# ICAN-7006-STM.net
KiCad netlist of a schematic drawn in Altium Designer
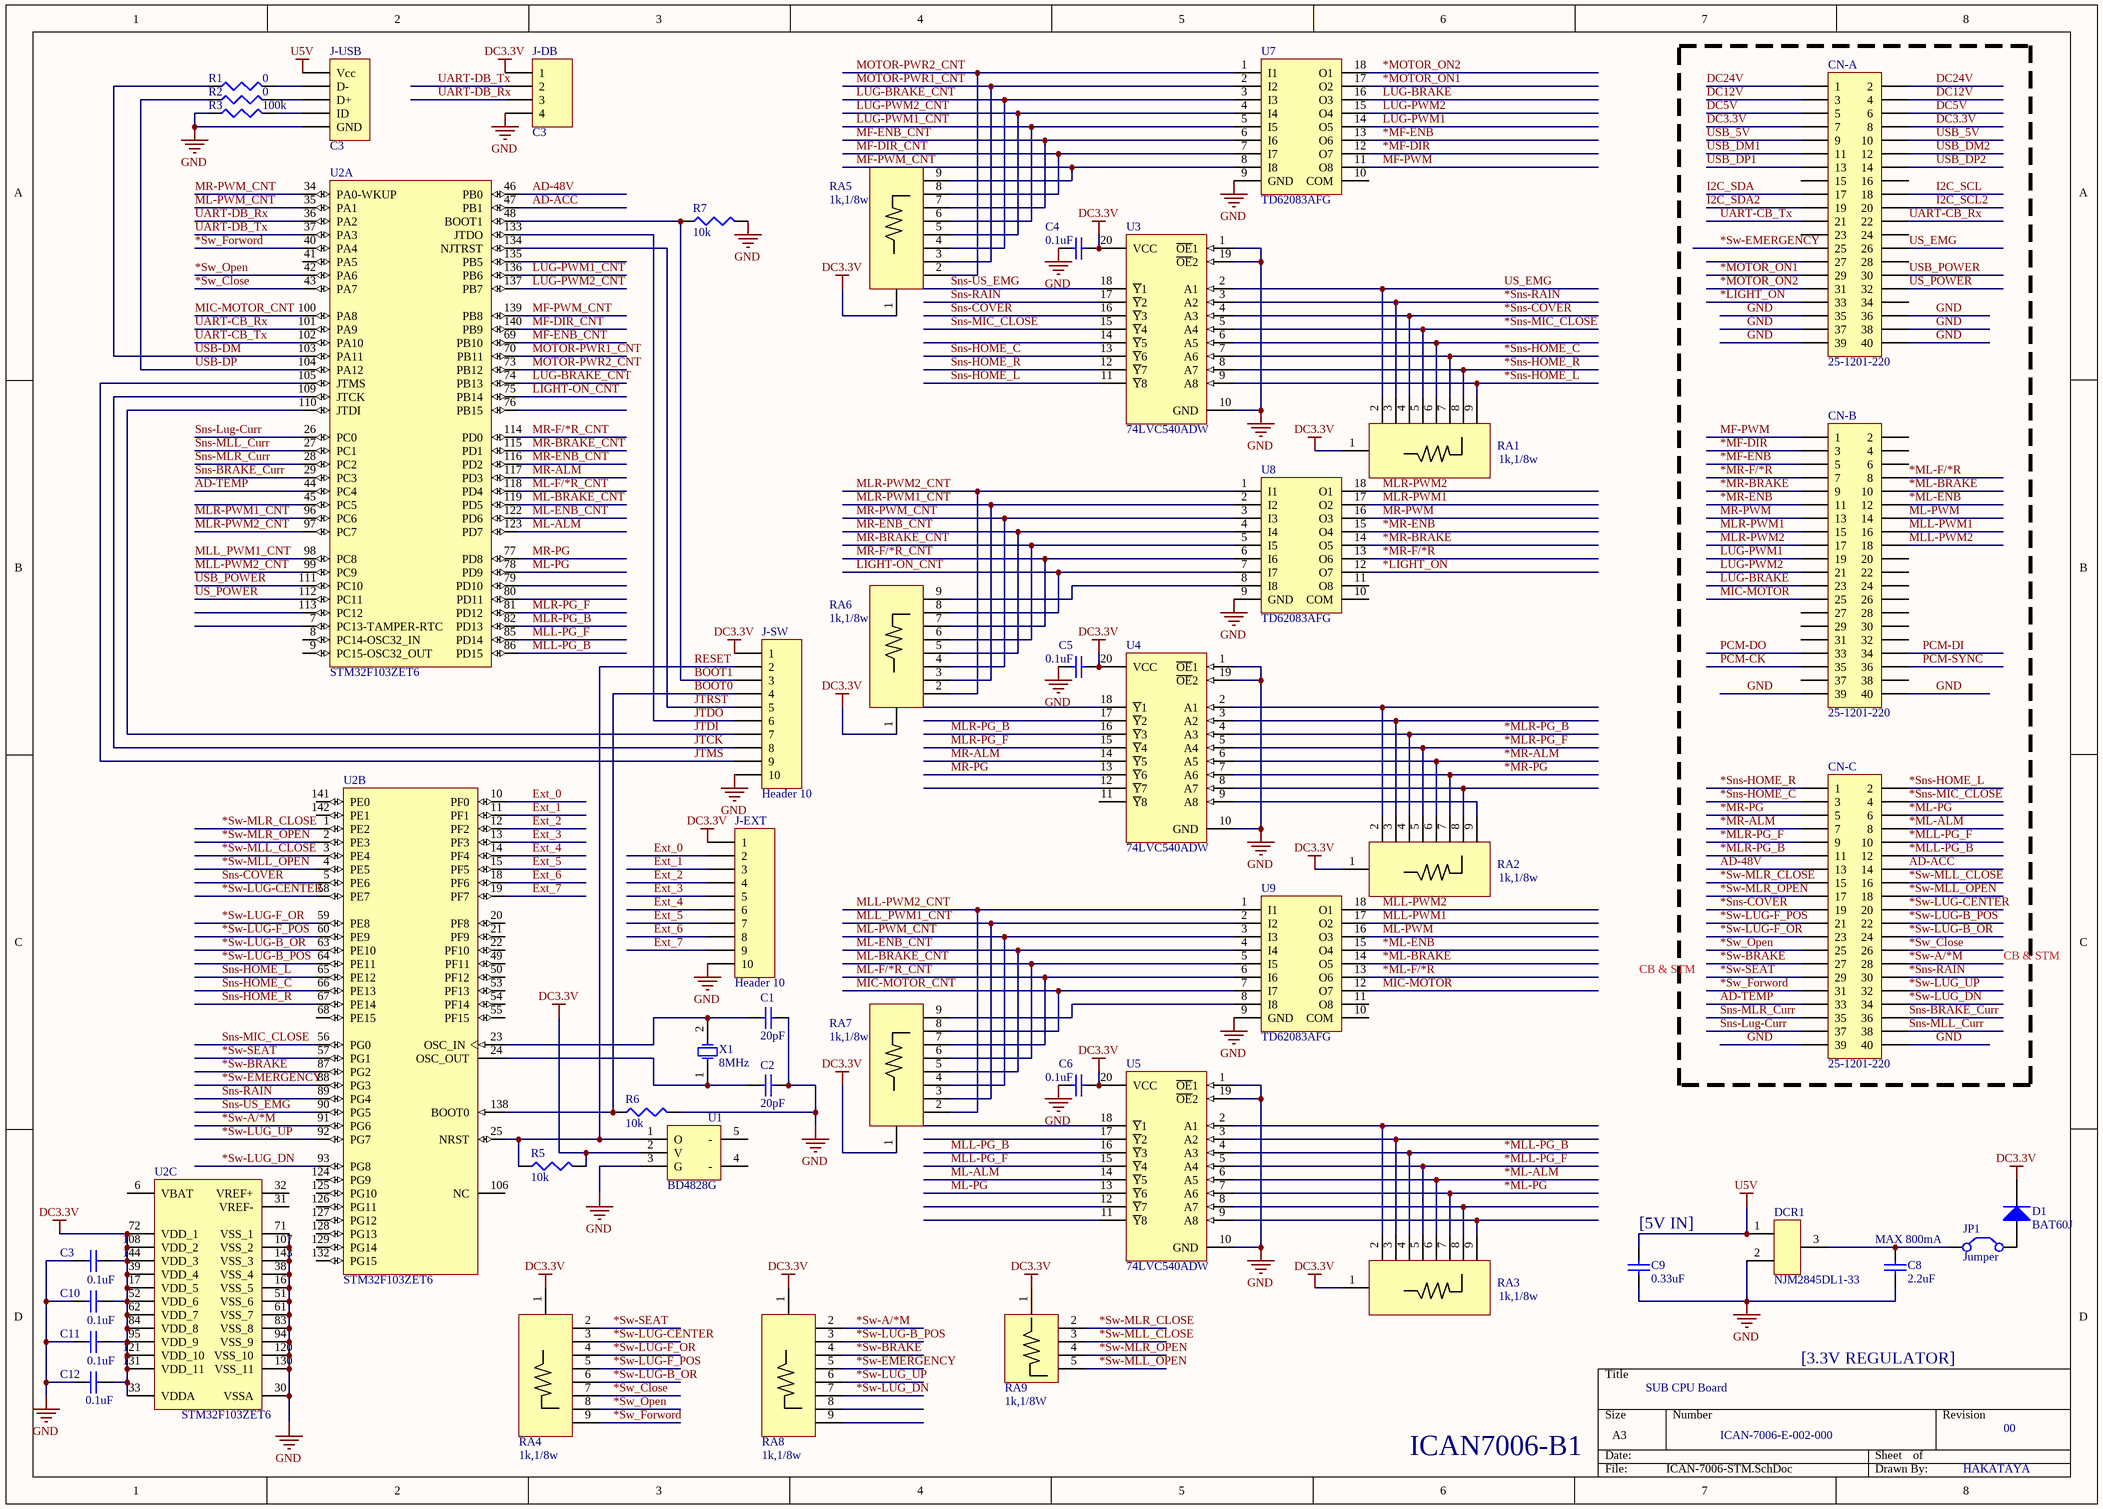
[diagram p0: ICAN-7006-STM.SchDoc]

(export (version "E")
  (design (tool "Eeschema 10.0.6"))
  (components
    (comp (ref "C1")
      (value "20pF")
      (footprint "HAKATAYA:[0805]2012")
      (description "Capacitor")
      (fields (field (name "PUBLISHER") "Altium Limited"))
      (libsource (lib "Miscellaneous Devices") (part "Cap Semi"))
    )
    (comp (ref "C2")
      (value "20pF")
      (footprint "[0805]2012")
      (description "Capacitor")
      (fields (field (name "PUBLISHER") "Altium Limited"))
      (libsource (lib "Miscellaneous Devices") (part "Cap Semi"))
    )
    (comp (ref "C3")
      (value "0.1uF")
      (footprint "[0805]2012")
      (description "Capacitor")
      (fields (field (name "PUBLISHER") "Altium Limited"))
      (libsource (lib "Miscellaneous Devices") (part "Cap Semi"))
    )
    (comp (ref "C4")
      (value "0.1uF")
      (footprint "[0805]2012")
      (description "Capacitor")
      (fields (field (name "PUBLISHER") "Altium Limited"))
      (libsource (lib "Miscellaneous Devices") (part "Cap"))
    )
    (comp (ref "C5")
      (value "0.1uF")
      (footprint "[0805]2012")
      (description "Capacitor")
      (fields (field (name "PUBLISHER") "Altium Limited"))
      (libsource (lib "Miscellaneous Devices") (part "Cap"))
    )
    (comp (ref "C6")
      (value "0.1uF")
      (footprint "[0805]2012")
      (description "Capacitor")
      (fields (field (name "PUBLISHER") "Altium Limited"))
      (libsource (lib "Miscellaneous Devices") (part "Cap"))
    )
    (comp (ref "C8")
      (value "2.2uF")
      (footprint "[0805]2012")
      (description "Capacitor")
      (fields (field (name "PUBLISHER") "Altium Limited"))
      (libsource (lib "Miscellaneous Devices") (part "Cap Semi"))
    )
    (comp (ref "C9")
      (value "0.33uF")
      (footprint "[0805]2012")
      (description "Capacitor")
      (fields (field (name "PUBLISHER") "Altium Limited"))
      (libsource (lib "Miscellaneous Devices") (part "Cap Semi"))
    )
    (comp (ref "C10")
      (value "0.1uF")
      (footprint "[0805]2012")
      (description "Capacitor")
      (fields (field (name "PUBLISHER") "Altium Limited"))
      (libsource (lib "Miscellaneous Devices") (part "Cap Semi"))
    )
    (comp (ref "C11")
      (value "0.1uF")
      (footprint "[0805]2012")
      (description "Capacitor")
      (fields (field (name "PUBLISHER") "Altium Limited"))
      (libsource (lib "Miscellaneous Devices") (part "Cap Semi"))
    )
    (comp (ref "C12")
      (value "0.1uF")
      (footprint "[0805]2012")
      (description "Capacitor")
      (fields (field (name "PUBLISHER") "Altium Limited"))
      (libsource (lib "Miscellaneous Devices") (part "Cap Semi"))
    )
    (comp (ref "CN-A")
      (value "25-1201-220")
      (footprint "HDR2X20")
      (description "Header, 20-Pin, Dual row")
      (fields (field (name "PUBLISHER") "Altium Limited"))
      (libsource (lib "Miscellaneous Connectors") (part "Header 20X2"))
    )
    (comp (ref "CN-B")
      (value "25-1201-220")
      (footprint "HDR2X20")
      (description "Header, 20-Pin, Dual row")
      (fields (field (name "PUBLISHER") "Altium Limited"))
      (libsource (lib "Miscellaneous Connectors") (part "Header 20X2"))
    )
    (comp (ref "CN-C")
      (value "25-1201-220")
      (footprint "HDR2X20")
      (description "Header, 20-Pin, Dual row")
      (fields (field (name "PUBLISHER") "Altium Limited"))
      (libsource (lib "Miscellaneous Connectors") (part "Header 20X2"))
    )
    (comp (ref "D1")
      (value "BAT60J")
      (footprint "HAKATAYA:[1107]2807 DIODE")
      (description "Default Diode")
      (fields (field (name "PUBLISHER") "Altium Limited"))
      (libsource (lib "Miscellaneous Devices") (part "Diode"))
    )
    (comp (ref "DCR1")
      (value "NJM2845DL1-33")
      (footprint "TO-252-3")
      (description "REGURATOR")
      (libsource (lib "HAKATAYA") (part "IC3"))
    )
    (comp (ref "J-DB")
      (value "C3")
      (footprint "HAKATAYA:C3-S4")
      (description "Header, 4-Pin")
      (fields (field (name "PUBLISHER") "Altium Limited"))
      (libsource (lib "Miscellaneous Connectors") (part "Header 4"))
    )
    (comp (ref "J-EXT")
      (value "Header 10")
      (footprint "HDR1X10")
      (description "Header, 10-Pin")
      (fields (field (name "PUBLISHER") "Altium Limited"))
      (libsource (lib "Miscellaneous Connectors") (part "Header 10"))
    )
    (comp (ref "J-SW")
      (value "Header 10")
      (footprint "HDR1X10")
      (description "Header, 10-Pin")
      (fields (field (name "PUBLISHER") "Altium Limited"))
      (libsource (lib "Miscellaneous Connectors") (part "Header 10"))
    )
    (comp (ref "J-USB")
      (value "C3")
      (footprint "HAKATAYA:C3-S5")
      (description "Header, 5-Pin")
      (fields (field (name "PUBLISHER") "Altium Limited"))
      (libsource (lib "Miscellaneous Connectors") (part "Header 5"))
    )
    (comp (ref "JP1")
      (value "Jumper")
      (footprint "Miscellaneous Devices:PIN2")
      (description "Jumper Wire")
      (fields (field (name "PUBLISHER") "Altium Limited"))
      (libsource (lib "Miscellaneous Devices") (part "Jumper"))
    )
    (comp (ref "R1")
      (value "0")
      (footprint "5025[2010]")
      (description "Resistor")
      (fields (field (name "PUBLISHER") "Altium Limited"))
      (libsource (lib "Miscellaneous Devices") (part "Res3"))
    )
    (comp (ref "R2")
      (value "0")
      (footprint "5025[2010]")
      (description "Resistor")
      (fields (field (name "PUBLISHER") "Altium Limited"))
      (libsource (lib "Miscellaneous Devices") (part "Res3"))
    )
    (comp (ref "R3")
      (value "100k")
      (footprint "5025[2010]")
      (description "Resistor")
      (fields (field (name "PUBLISHER") "Altium Limited"))
      (libsource (lib "Miscellaneous Devices") (part "Res3"))
    )
    (comp (ref "R5")
      (value "10k")
      (footprint "[0805]2012")
      (description "Resistor")
      (fields (field (name "PUBLISHER") "Altium Limited"))
      (libsource (lib "Miscellaneous Devices") (part "Res3"))
    )
    (comp (ref "R6")
      (value "10k")
      (footprint "[0805]2012")
      (description "Resistor")
      (fields (field (name "PUBLISHER") "Altium Limited"))
      (libsource (lib "Miscellaneous Devices") (part "Res3"))
    )
    (comp (ref "R7")
      (value "10k")
      (footprint "[0805]2012")
      (description "Resistor")
      (fields (field (name "PUBLISHER") "Altium Limited"))
      (libsource (lib "Miscellaneous Devices") (part "Res3"))
    )
    (comp (ref "RA1")
      (value "1k,1/8w")
      (footprint "SIP 9p")
      (description "Resistor arrey")
      (libsource (lib "HAKATAYA") (part "RES 8P"))
    )
    (comp (ref "RA2")
      (value "1k,1/8w")
      (footprint "SIP 9p")
      (description "Resistor arrey")
      (libsource (lib "HAKATAYA") (part "RES 8P"))
    )
    (comp (ref "RA3")
      (value "1k,1/8w")
      (footprint "SIP 9p")
      (description "Resistor arrey")
      (libsource (lib "HAKATAYA") (part "RES 8P"))
    )
    (comp (ref "RA4")
      (value "1k,1/8w")
      (footprint "SIP 9p")
      (description "Resistor arrey")
      (libsource (lib "") (part "RES 8P_2"))
    )
    (comp (ref "RA5")
      (value "1k,1/8w")
      (footprint "SIP 9p")
      (description "Resistor arrey")
      (libsource (lib "") (part "RES 8P_1"))
    )
    (comp (ref "RA6")
      (value "1k,1/8w")
      (footprint "SIP 9p")
      (description "Resistor arrey")
      (libsource (lib "") (part "RES 8P_1"))
    )
    (comp (ref "RA7")
      (value "1k,1/8w")
      (footprint "SIP 9p")
      (description "Resistor arrey")
      (libsource (lib "") (part "RES 8P_1"))
    )
    (comp (ref "RA8")
      (value "1k,1/8w")
      (footprint "SIP 9p")
      (description "Resistor arrey")
      (libsource (lib "") (part "RES 8P_2"))
    )
    (comp (ref "RA9")
      (value "1k,1/8W")
      (footprint "SIP 5P")
      (description "Resistor arrey")
      (libsource (lib "HAKATAYA") (part "RES 4P"))
    )
    (comp (ref "U1")
      (value "BD4828G")
      (footprint "HAKATAYA:PST596")
      (description "RESET IC")
      (libsource (lib "HAKATAYA") (part "IC5-WIDE"))
    )
    (comp (ref "U2")
      (value "STM32F103ZET6")
      (footprint "STM-LQFP144_L")
      (libsource (lib "STMicroelectronics STM32 F1") (part "STM32F103ZET6"))
    )
    (comp (ref "U3")
      (value "74LVC540ADW")
      (footprint "SO-20")
      (description "Octal Buffer and Line Driver with 3-State Outputs")
      (fields (field (name "PUBLISHER") "Altium Limited"))
      (libsource (lib "TI Logic Buffer Line Driver") (part "SN74LS540N"))
    )
    (comp (ref "U4")
      (value "74LVC540ADW")
      (footprint "SO-20")
      (description "Octal Buffer and Line Driver with 3-State Outputs")
      (fields (field (name "PUBLISHER") "Altium Limited"))
      (libsource (lib "TI Logic Buffer Line Driver") (part "SN74LS540N"))
    )
    (comp (ref "U5")
      (value "74LVC540ADW")
      (footprint "SO-20")
      (description "Octal Buffer and Line Driver with 3-State Outputs")
      (fields (field (name "PUBLISHER") "Altium Limited"))
      (libsource (lib "TI Logic Buffer Line Driver") (part "SN74LS540N"))
    )
    (comp (ref "U7")
      (value "TD62083AFG")
      (footprint "TD6208X(SOP)")
      (description "Driver")
      (libsource (lib "*") (part "TD62083"))
    )
    (comp (ref "U8")
      (value "TD62083AFG")
      (footprint "TD6208X(SOP)")
      (description "Driver")
      (libsource (lib "*") (part "TD62083"))
    )
    (comp (ref "U9")
      (value "TD62083AFG")
      (footprint "TD6208X(SOP)")
      (description "Driver")
      (libsource (lib "*") (part "TD62083"))
    )
    (comp (ref "X1")
      (value "8MHz")
      (footprint "HAKATAYA:CRYSTAL 49S")
      (description "Crystal Oscillator")
      (fields (field (name "PUBLISHER") "Altium Limited"))
      (libsource (lib "Miscellaneous Devices") (part "XTAL"))
    )
  )
  (nets
    (net (code "1") (name "/*LIGHT_ON") (class "Default")
      (node (ref "CN-A") (pin "33") (pinfunction "33_33") (pintype "passive"))
      (node (ref "U8") (pin "12") (pinfunction "O7_12") (pintype "passive"))
    )
    (net (code "2") (name "/*MF-DIR") (class "Default")
      (node (ref "CN-B") (pin "3") (pinfunction "3_3") (pintype "passive"))
      (node (ref "U7") (pin "12") (pinfunction "O7_12") (pintype "passive"))
    )
    (net (code "3") (name "/*MF-ENB") (class "Default")
      (node (ref "CN-B") (pin "5") (pinfunction "5_5") (pintype "passive"))
      (node (ref "U7") (pin "13") (pinfunction "O6_13") (pintype "passive"))
    )
    (net (code "4") (name "/*ML-ALM") (class "Default")
      (node (ref "CN-C") (pin "8") (pinfunction "8_8") (pintype "passive"))
      (node (ref "RA3") (pin "6") (pinfunction "6_6") (pintype "passive"))
      (node (ref "U5") (pin "6") (pinfunction "A5_6") (pintype "input"))
    )
    (net (code "5") (name "/*ML-BRAKE") (class "Default")
      (node (ref "CN-B") (pin "10") (pinfunction "10_10") (pintype "passive"))
      (node (ref "U9") (pin "14") (pinfunction "O5_14") (pintype "passive"))
    )
    (net (code "6") (name "/*ML-ENB") (class "Default")
      (node (ref "CN-B") (pin "12") (pinfunction "12_12") (pintype "passive"))
      (node (ref "U9") (pin "15") (pinfunction "O4_15") (pintype "passive"))
    )
    (net (code "7") (name "/*ML-F{slash}*R") (class "Default")
      (node (ref "CN-B") (pin "8") (pinfunction "8_8") (pintype "passive"))
      (node (ref "U9") (pin "13") (pinfunction "O6_13") (pintype "passive"))
    )
    (net (code "8") (name "/*ML-PG") (class "Default")
      (node (ref "CN-C") (pin "6") (pinfunction "6_6") (pintype "passive"))
      (node (ref "RA3") (pin "7") (pinfunction "7_7") (pintype "passive"))
      (node (ref "U5") (pin "7") (pinfunction "A6_7") (pintype "input"))
    )
    (net (code "9") (name "/*MLL-PG_B") (class "Default")
      (node (ref "CN-C") (pin "12") (pinfunction "12_12") (pintype "passive"))
      (node (ref "RA3") (pin "4") (pinfunction "4_4") (pintype "passive"))
      (node (ref "U5") (pin "4") (pinfunction "A3_4") (pintype "input"))
    )
    (net (code "10") (name "/*MLL-PG_F") (class "Default")
      (node (ref "CN-C") (pin "10") (pinfunction "10_10") (pintype "passive"))
      (node (ref "RA3") (pin "5") (pinfunction "5_5") (pintype "passive"))
      (node (ref "U5") (pin "5") (pinfunction "A4_5") (pintype "input"))
    )
    (net (code "11") (name "/*MLR-PG_B") (class "Default")
      (node (ref "CN-C") (pin "11") (pinfunction "11_11") (pintype "passive"))
      (node (ref "RA2") (pin "4") (pinfunction "4_4") (pintype "passive"))
      (node (ref "U4") (pin "4") (pinfunction "A3_4") (pintype "input"))
    )
    (net (code "12") (name "/*MLR-PG_F") (class "Default")
      (node (ref "CN-C") (pin "9") (pinfunction "9_9") (pintype "passive"))
      (node (ref "RA2") (pin "5") (pinfunction "5_5") (pintype "passive"))
      (node (ref "U4") (pin "5") (pinfunction "A4_5") (pintype "input"))
    )
    (net (code "13") (name "/*MOTOR_ON1") (class "Default")
      (node (ref "CN-A") (pin "29") (pinfunction "29_29") (pintype "passive"))
      (node (ref "U7") (pin "17") (pinfunction "O2_17") (pintype "passive"))
    )
    (net (code "14") (name "/*MOTOR_ON2") (class "Default")
      (node (ref "CN-A") (pin "31") (pinfunction "31_31") (pintype "passive"))
      (node (ref "U7") (pin "18") (pinfunction "O1_18") (pintype "passive"))
    )
    (net (code "15") (name "/*MR-ALM") (class "Default")
      (node (ref "CN-C") (pin "7") (pinfunction "7_7") (pintype "passive"))
      (node (ref "RA2") (pin "6") (pinfunction "6_6") (pintype "passive"))
      (node (ref "U4") (pin "6") (pinfunction "A5_6") (pintype "input"))
    )
    (net (code "16") (name "/*MR-BRAKE") (class "Default")
      (node (ref "CN-B") (pin "9") (pinfunction "9_9") (pintype "passive"))
      (node (ref "U8") (pin "14") (pinfunction "O5_14") (pintype "passive"))
    )
    (net (code "17") (name "/*MR-ENB") (class "Default")
      (node (ref "CN-B") (pin "11") (pinfunction "11_11") (pintype "passive"))
      (node (ref "U8") (pin "15") (pinfunction "O4_15") (pintype "passive"))
    )
    (net (code "18") (name "/*MR-F{slash}*R") (class "Default")
      (node (ref "CN-B") (pin "7") (pinfunction "7_7") (pintype "passive"))
      (node (ref "U8") (pin "13") (pinfunction "O6_13") (pintype "passive"))
    )
    (net (code "19") (name "/*MR-PG") (class "Default")
      (node (ref "CN-C") (pin "5") (pinfunction "5_5") (pintype "passive"))
      (node (ref "RA2") (pin "7") (pinfunction "7_7") (pintype "passive"))
      (node (ref "U4") (pin "7") (pinfunction "A6_7") (pintype "input"))
    )
    (net (code "20") (name "/*Sns-COVER") (class "Default")
      (node (ref "CN-C") (pin "19") (pinfunction "19_19") (pintype "passive"))
      (node (ref "RA1") (pin "4") (pinfunction "4_4") (pintype "passive"))
      (node (ref "U3") (pin "4") (pinfunction "A3_4") (pintype "input"))
    )
    (net (code "21") (name "/*Sns-HOME_C") (class "Default")
      (node (ref "CN-C") (pin "3") (pinfunction "3_3") (pintype "passive"))
      (node (ref "RA1") (pin "7") (pinfunction "7_7") (pintype "passive"))
      (node (ref "U3") (pin "7") (pinfunction "A6_7") (pintype "input"))
    )
    (net (code "22") (name "/*Sns-HOME_L") (class "Default")
      (node (ref "CN-C") (pin "2") (pinfunction "2_2") (pintype "passive"))
      (node (ref "RA1") (pin "9") (pinfunction "9_9") (pintype "passive"))
      (node (ref "U3") (pin "9") (pinfunction "A8_9") (pintype "input"))
    )
    (net (code "23") (name "/*Sns-HOME_R") (class "Default")
      (node (ref "CN-C") (pin "1") (pinfunction "1_1") (pintype "passive"))
      (node (ref "RA1") (pin "8") (pinfunction "8_8") (pintype "passive"))
      (node (ref "U3") (pin "8") (pinfunction "A7_8") (pintype "input"))
    )
    (net (code "24") (name "/*Sns-MIC_CLOSE") (class "Default")
      (node (ref "CN-C") (pin "4") (pinfunction "4_4") (pintype "passive"))
      (node (ref "RA1") (pin "5") (pinfunction "5_5") (pintype "passive"))
      (node (ref "U3") (pin "5") (pinfunction "A4_5") (pintype "input"))
    )
    (net (code "25") (name "/*Sns-RAIN") (class "Default")
      (node (ref "CN-C") (pin "30") (pinfunction "30_30") (pintype "passive"))
      (node (ref "RA1") (pin "3") (pinfunction "3_3") (pintype "passive"))
      (node (ref "U3") (pin "3") (pinfunction "A2_3") (pintype "input"))
    )
    (net (code "26") (name "/*Sw-A{slash}*M") (class "Default")
      (node (ref "CN-C") (pin "28") (pinfunction "28_28") (pintype "passive"))
      (node (ref "RA8") (pin "2") (pinfunction "2_2") (pintype "passive"))
      (node (ref "U2") (pin "91") (pinfunction "PG6_91") (pintype "bidirectional"))
    )
    (net (code "27") (name "/*Sw-BRAKE") (class "Default")
      (node (ref "CN-C") (pin "27") (pinfunction "27_27") (pintype "passive"))
      (node (ref "RA8") (pin "4") (pinfunction "4_4") (pintype "passive"))
      (node (ref "U2") (pin "87") (pinfunction "PG2_87") (pintype "bidirectional"))
    )
    (net (code "28") (name "/*Sw-EMERGENCY") (class "Default")
      (node (ref "CN-A") (pin "25") (pinfunction "25_25") (pintype "passive"))
      (node (ref "RA8") (pin "5") (pinfunction "5_5") (pintype "passive"))
      (node (ref "U2") (pin "88") (pinfunction "PG3_88") (pintype "bidirectional"))
    )
    (net (code "29") (name "/*Sw-LUG-B_OR") (class "Default")
      (node (ref "CN-C") (pin "24") (pinfunction "24_24") (pintype "passive"))
      (node (ref "RA4") (pin "6") (pinfunction "6_6") (pintype "passive"))
      (node (ref "U2") (pin "63") (pinfunction "PE10_63") (pintype "bidirectional"))
    )
    (net (code "30") (name "/*Sw-LUG-B_POS") (class "Default")
      (node (ref "CN-C") (pin "22") (pinfunction "22_22") (pintype "passive"))
      (node (ref "RA8") (pin "3") (pinfunction "3_3") (pintype "passive"))
      (node (ref "U2") (pin "64") (pinfunction "PE11_64") (pintype "bidirectional"))
    )
    (net (code "31") (name "/*Sw-LUG-CENTER") (class "Default")
      (node (ref "CN-C") (pin "20") (pinfunction "20_20") (pintype "passive"))
      (node (ref "RA4") (pin "3") (pinfunction "3_3") (pintype "passive"))
      (node (ref "U2") (pin "58") (pinfunction "PE7_58") (pintype "bidirectional"))
    )
    (net (code "32") (name "/*Sw-LUG-F_OR") (class "Default")
      (node (ref "CN-C") (pin "23") (pinfunction "23_23") (pintype "passive"))
      (node (ref "RA4") (pin "4") (pinfunction "4_4") (pintype "passive"))
      (node (ref "U2") (pin "59") (pinfunction "PE8_59") (pintype "bidirectional"))
    )
    (net (code "33") (name "/*Sw-LUG-F_POS") (class "Default")
      (node (ref "CN-C") (pin "21") (pinfunction "21_21") (pintype "passive"))
      (node (ref "RA4") (pin "5") (pinfunction "5_5") (pintype "passive"))
      (node (ref "U2") (pin "60") (pinfunction "PE9_60") (pintype "bidirectional"))
    )
    (net (code "34") (name "/*Sw-LUG_DN") (class "Default")
      (node (ref "CN-C") (pin "34") (pinfunction "34_34") (pintype "passive"))
      (node (ref "RA8") (pin "7") (pinfunction "7_7") (pintype "passive"))
      (node (ref "U2") (pin "93") (pinfunction "PG8_93") (pintype "bidirectional"))
    )
    (net (code "35") (name "/*Sw-LUG_UP") (class "Default")
      (node (ref "CN-C") (pin "32") (pinfunction "32_32") (pintype "passive"))
      (node (ref "RA8") (pin "6") (pinfunction "6_6") (pintype "passive"))
      (node (ref "U2") (pin "92") (pinfunction "PG7_92") (pintype "bidirectional"))
    )
    (net (code "36") (name "/*Sw-MLL_CLOSE") (class "Default")
      (node (ref "CN-C") (pin "16") (pinfunction "16_16") (pintype "passive"))
      (node (ref "RA9") (pin "3") (pinfunction "3_3") (pintype "passive"))
      (node (ref "U2") (pin "3") (pinfunction "PE4_3") (pintype "bidirectional"))
    )
    (net (code "37") (name "/*Sw-MLL_OPEN") (class "Default")
      (node (ref "CN-C") (pin "18") (pinfunction "18_18") (pintype "passive"))
      (node (ref "RA9") (pin "5") (pinfunction "5_5") (pintype "passive"))
      (node (ref "U2") (pin "4") (pinfunction "PE5_4") (pintype "bidirectional"))
    )
    (net (code "38") (name "/*Sw-MLR_CLOSE") (class "Default")
      (node (ref "CN-C") (pin "15") (pinfunction "15_15") (pintype "passive"))
      (node (ref "RA9") (pin "2") (pinfunction "2_2") (pintype "passive"))
      (node (ref "U2") (pin "1") (pinfunction "PE2_1") (pintype "bidirectional"))
    )
    (net (code "39") (name "/*Sw-MLR_OPEN") (class "Default")
      (node (ref "CN-C") (pin "17") (pinfunction "17_17") (pintype "passive"))
      (node (ref "RA9") (pin "4") (pinfunction "4_4") (pintype "passive"))
      (node (ref "U2") (pin "2") (pinfunction "PE3_2") (pintype "bidirectional"))
    )
    (net (code "40") (name "/*Sw-SEAT") (class "Default")
      (node (ref "CN-C") (pin "29") (pinfunction "29_29") (pintype "passive"))
      (node (ref "RA4") (pin "2") (pinfunction "2_2") (pintype "passive"))
      (node (ref "U2") (pin "57") (pinfunction "PG1_57") (pintype "bidirectional"))
    )
    (net (code "41") (name "/*Sw_Close") (class "Default")
      (node (ref "CN-C") (pin "26") (pinfunction "26_26") (pintype "passive"))
      (node (ref "RA4") (pin "7") (pinfunction "7_7") (pintype "passive"))
      (node (ref "U2") (pin "43") (pinfunction "PA7_43") (pintype "bidirectional"))
    )
    (net (code "42") (name "/*Sw_Forword") (class "Default")
      (node (ref "CN-C") (pin "31") (pinfunction "31_31") (pintype "passive"))
      (node (ref "RA4") (pin "9") (pinfunction "9_9") (pintype "passive"))
      (node (ref "U2") (pin "40") (pinfunction "PA4_40") (pintype "bidirectional"))
    )
    (net (code "43") (name "/*Sw_Open") (class "Default")
      (node (ref "CN-C") (pin "25") (pinfunction "25_25") (pintype "passive"))
      (node (ref "RA4") (pin "8") (pinfunction "8_8") (pintype "passive"))
      (node (ref "U2") (pin "42") (pinfunction "PA6_42") (pintype "bidirectional"))
    )
    (net (code "44") (name "/AD-48V") (class "Default")
      (node (ref "CN-C") (pin "13") (pinfunction "13_13") (pintype "passive"))
      (node (ref "U2") (pin "46") (pinfunction "PB0_46") (pintype "bidirectional"))
    )
    (net (code "45") (name "/AD-ACC") (class "Default")
      (node (ref "CN-C") (pin "14") (pinfunction "14_14") (pintype "passive"))
      (node (ref "U2") (pin "47") (pinfunction "PB1_47") (pintype "bidirectional"))
    )
    (net (code "46") (name "/AD-TEMP") (class "Default")
      (node (ref "CN-C") (pin "33") (pinfunction "33_33") (pintype "passive"))
      (node (ref "U2") (pin "44") (pinfunction "PC4_44") (pintype "bidirectional"))
    )
    (net (code "47") (name "/BOOT0") (class "Default")
      (node (ref "J-SW") (pin "4") (pinfunction "4_4") (pintype "passive"))
      (node (ref "R6") (pin "1") (pinfunction "1_1") (pintype "passive"))
      (node (ref "U2") (pin "138") (pinfunction "BOOT0_138") (pintype "input"))
    )
    (net (code "48") (name "/BOOT1") (class "Default")
      (node (ref "J-SW") (pin "3") (pinfunction "3_3") (pintype "passive"))
      (node (ref "R7") (pin "1") (pinfunction "1_1") (pintype "passive"))
      (node (ref "U2") (pin "48") (pinfunction "BOOT1_48") (pintype "bidirectional"))
    )
    (net (code "49") (name "/DC5V") (class "Default")
      (node (ref "CN-A") (pin "5") (pinfunction "5_5") (pintype "passive"))
      (node (ref "CN-A") (pin "6") (pinfunction "6_6") (pintype "passive"))
    )
    (net (code "50") (name "/DC12V") (class "Default")
      (node (ref "CN-A") (pin "3") (pinfunction "3_3") (pintype "passive"))
      (node (ref "CN-A") (pin "4") (pinfunction "4_4") (pintype "passive"))
    )
    (net (code "51") (name "/DC24V") (class "Default")
      (node (ref "CN-A") (pin "1") (pinfunction "1_1") (pintype "passive"))
      (node (ref "CN-A") (pin "2") (pinfunction "2_2") (pintype "passive"))
    )
    (net (code "52") (name "/Ext_0") (class "Default")
      (node (ref "J-EXT") (pin "2") (pinfunction "2_2") (pintype "passive"))
      (node (ref "U2") (pin "10") (pinfunction "PF0_10") (pintype "bidirectional"))
    )
    (net (code "53") (name "/Ext_1") (class "Default")
      (node (ref "J-EXT") (pin "3") (pinfunction "3_3") (pintype "passive"))
      (node (ref "U2") (pin "11") (pinfunction "PF1_11") (pintype "bidirectional"))
    )
    (net (code "54") (name "/Ext_2") (class "Default")
      (node (ref "J-EXT") (pin "4") (pinfunction "4_4") (pintype "passive"))
      (node (ref "U2") (pin "12") (pinfunction "PF2_12") (pintype "bidirectional"))
    )
    (net (code "55") (name "/Ext_3") (class "Default")
      (node (ref "J-EXT") (pin "5") (pinfunction "5_5") (pintype "passive"))
      (node (ref "U2") (pin "13") (pinfunction "PF3_13") (pintype "bidirectional"))
    )
    (net (code "56") (name "/Ext_4") (class "Default")
      (node (ref "J-EXT") (pin "6") (pinfunction "6_6") (pintype "passive"))
      (node (ref "U2") (pin "14") (pinfunction "PF4_14") (pintype "bidirectional"))
    )
    (net (code "57") (name "/Ext_5") (class "Default")
      (node (ref "J-EXT") (pin "7") (pinfunction "7_7") (pintype "passive"))
      (node (ref "U2") (pin "15") (pinfunction "PF5_15") (pintype "bidirectional"))
    )
    (net (code "58") (name "/Ext_6") (class "Default")
      (node (ref "J-EXT") (pin "8") (pinfunction "8_8") (pintype "passive"))
      (node (ref "U2") (pin "18") (pinfunction "PF6_18") (pintype "bidirectional"))
    )
    (net (code "59") (name "/Ext_7") (class "Default")
      (node (ref "J-EXT") (pin "9") (pinfunction "9_9") (pintype "passive"))
      (node (ref "U2") (pin "19") (pinfunction "PF7_19") (pintype "bidirectional"))
    )
    (net (code "60") (name "/I2C_SCL") (class "Default")
      (node (ref "CN-A") (pin "18") (pinfunction "18_18") (pintype "passive"))
    )
    (net (code "61") (name "/I2C_SCL2") (class "Default")
      (node (ref "CN-A") (pin "20") (pinfunction "20_20") (pintype "passive"))
    )
    (net (code "62") (name "/I2C_SDA") (class "Default")
      (node (ref "CN-A") (pin "17") (pinfunction "17_17") (pintype "passive"))
    )
    (net (code "63") (name "/I2C_SDA2") (class "Default")
      (node (ref "CN-A") (pin "19") (pinfunction "19_19") (pintype "passive"))
    )
    (net (code "64") (name "/JTCK") (class "Default")
      (node (ref "J-SW") (pin "8") (pinfunction "8_8") (pintype "passive"))
      (node (ref "U2") (pin "109") (pinfunction "JTCK_109") (pintype "bidirectional"))
    )
    (net (code "65") (name "/JTDI") (class "Default")
      (node (ref "J-SW") (pin "7") (pinfunction "7_7") (pintype "passive"))
      (node (ref "U2") (pin "110") (pinfunction "JTDI_110") (pintype "bidirectional"))
    )
    (net (code "66") (name "/JTDO") (class "Default")
      (node (ref "J-SW") (pin "6") (pinfunction "6_6") (pintype "passive"))
      (node (ref "U2") (pin "133") (pinfunction "JTDO_133") (pintype "bidirectional"))
    )
    (net (code "67") (name "/JTMS") (class "Default")
      (node (ref "J-SW") (pin "9") (pinfunction "9_9") (pintype "passive"))
      (node (ref "U2") (pin "105") (pinfunction "JTMS_105") (pintype "bidirectional"))
    )
    (net (code "68") (name "/JTRST") (class "Default")
      (node (ref "J-SW") (pin "5") (pinfunction "5_5") (pintype "passive"))
      (node (ref "U2") (pin "134") (pinfunction "NJTRST_134") (pintype "bidirectional"))
    )
    (net (code "69") (name "/LIGHT-ON_CNT") (class "Default")
      (node (ref "RA6") (pin "8") (pinfunction "8_8") (pintype "passive"))
      (node (ref "U2") (pin "75") (pinfunction "PB14_75") (pintype "bidirectional"))
      (node (ref "U8") (pin "7") (pinfunction "I7_7") (pintype "passive"))
    )
    (net (code "70") (name "/LUG-BRAKE") (class "Default")
      (node (ref "CN-B") (pin "23") (pinfunction "23_23") (pintype "passive"))
      (node (ref "U7") (pin "16") (pinfunction "O3_16") (pintype "passive"))
    )
    (net (code "71") (name "/LUG-BRAKE_CNT") (class "Default")
      (node (ref "RA5") (pin "4") (pinfunction "4_4") (pintype "passive"))
      (node (ref "U2") (pin "74") (pinfunction "PB13_74") (pintype "bidirectional"))
      (node (ref "U7") (pin "3") (pinfunction "I3_3") (pintype "passive"))
    )
    (net (code "72") (name "/LUG-PWM1") (class "Default")
      (node (ref "CN-B") (pin "19") (pinfunction "19_19") (pintype "passive"))
      (node (ref "U7") (pin "14") (pinfunction "O5_14") (pintype "passive"))
    )
    (net (code "73") (name "/LUG-PWM1_CNT") (class "Default")
      (node (ref "RA5") (pin "6") (pinfunction "6_6") (pintype "passive"))
      (node (ref "U2") (pin "136") (pinfunction "PB6_136") (pintype "bidirectional"))
      (node (ref "U7") (pin "5") (pinfunction "I5_5") (pintype "passive"))
    )
    (net (code "74") (name "/LUG-PWM2") (class "Default")
      (node (ref "CN-B") (pin "21") (pinfunction "21_21") (pintype "passive"))
      (node (ref "U7") (pin "15") (pinfunction "O4_15") (pintype "passive"))
    )
    (net (code "75") (name "/LUG-PWM2_CNT") (class "Default")
      (node (ref "RA5") (pin "5") (pinfunction "5_5") (pintype "passive"))
      (node (ref "U2") (pin "137") (pinfunction "PB7_137") (pintype "bidirectional"))
      (node (ref "U7") (pin "4") (pinfunction "I4_4") (pintype "passive"))
    )
    (net (code "76") (name "/MF-DIR_CNT") (class "Default")
      (node (ref "RA5") (pin "8") (pinfunction "8_8") (pintype "passive"))
      (node (ref "U2") (pin "140") (pinfunction "PB9_140") (pintype "bidirectional"))
      (node (ref "U7") (pin "7") (pinfunction "I7_7") (pintype "passive"))
    )
    (net (code "77") (name "/MF-ENB_CNT") (class "Default")
      (node (ref "RA5") (pin "7") (pinfunction "7_7") (pintype "passive"))
      (node (ref "U2") (pin "69") (pinfunction "PB10_69") (pintype "bidirectional"))
      (node (ref "U7") (pin "6") (pinfunction "I6_6") (pintype "passive"))
    )
    (net (code "78") (name "/MF-PWM") (class "Default")
      (node (ref "CN-B") (pin "1") (pinfunction "1_1") (pintype "passive"))
      (node (ref "U7") (pin "11") (pinfunction "O8_11") (pintype "passive"))
    )
    (net (code "79") (name "/MF-PWM_CNT") (class "Default")
      (node (ref "RA5") (pin "9") (pinfunction "9_9") (pintype "passive"))
      (node (ref "U2") (pin "139") (pinfunction "PB8_139") (pintype "bidirectional"))
      (node (ref "U7") (pin "8") (pinfunction "I8_8") (pintype "passive"))
    )
    (net (code "80") (name "/MIC-MOTOR") (class "Default")
      (node (ref "CN-B") (pin "25") (pinfunction "25_25") (pintype "passive"))
      (node (ref "U9") (pin "12") (pinfunction "O7_12") (pintype "passive"))
    )
    (net (code "81") (name "/MIC-MOTOR_CNT") (class "Default")
      (node (ref "RA7") (pin "8") (pinfunction "8_8") (pintype "passive"))
      (node (ref "U2") (pin "100") (pinfunction "PA8_100") (pintype "bidirectional"))
      (node (ref "U9") (pin "7") (pinfunction "I7_7") (pintype "passive"))
    )
    (net (code "82") (name "/ML-ALM") (class "Default")
      (node (ref "U2") (pin "123") (pinfunction "PD7_123") (pintype "bidirectional"))
      (node (ref "U5") (pin "14") (pinfunction "~{Y}5_14") (pintype "tri_state"))
    )
    (net (code "83") (name "/ML-BRAKE_CNT") (class "Default")
      (node (ref "RA7") (pin "6") (pinfunction "6_6") (pintype "passive"))
      (node (ref "U2") (pin "119") (pinfunction "PD5_119") (pintype "bidirectional"))
      (node (ref "U9") (pin "5") (pinfunction "I5_5") (pintype "passive"))
    )
    (net (code "84") (name "/ML-ENB_CNT") (class "Default")
      (node (ref "RA7") (pin "5") (pinfunction "5_5") (pintype "passive"))
      (node (ref "U2") (pin "122") (pinfunction "PD6_122") (pintype "bidirectional"))
      (node (ref "U9") (pin "4") (pinfunction "I4_4") (pintype "passive"))
    )
    (net (code "85") (name "/ML-F{slash}*R_CNT") (class "Default")
      (node (ref "RA7") (pin "7") (pinfunction "7_7") (pintype "passive"))
      (node (ref "U2") (pin "118") (pinfunction "PD4_118") (pintype "bidirectional"))
      (node (ref "U9") (pin "6") (pinfunction "I6_6") (pintype "passive"))
    )
    (net (code "86") (name "/ML-PG") (class "Default")
      (node (ref "U2") (pin "78") (pinfunction "PD9_78") (pintype "bidirectional"))
      (node (ref "U5") (pin "13") (pinfunction "~{Y}6_13") (pintype "tri_state"))
    )
    (net (code "87") (name "/ML-PWM") (class "Default")
      (node (ref "CN-B") (pin "14") (pinfunction "14_14") (pintype "passive"))
      (node (ref "U9") (pin "16") (pinfunction "O3_16") (pintype "passive"))
    )
    (net (code "88") (name "/ML-PWM_CNT") (class "Default")
      (node (ref "RA7") (pin "4") (pinfunction "4_4") (pintype "passive"))
      (node (ref "U2") (pin "35") (pinfunction "PA1_35") (pintype "bidirectional"))
      (node (ref "U9") (pin "3") (pinfunction "I3_3") (pintype "passive"))
    )
    (net (code "89") (name "/MLL-PG_B") (class "Default")
      (node (ref "U2") (pin "86") (pinfunction "PD15_86") (pintype "bidirectional"))
      (node (ref "U5") (pin "16") (pinfunction "~{Y}3_16") (pintype "tri_state"))
    )
    (net (code "90") (name "/MLL-PG_F") (class "Default")
      (node (ref "U2") (pin "85") (pinfunction "PD14_85") (pintype "bidirectional"))
      (node (ref "U5") (pin "15") (pinfunction "~{Y}4_15") (pintype "tri_state"))
    )
    (net (code "91") (name "/MLL-PWM1") (class "Default")
      (node (ref "CN-B") (pin "16") (pinfunction "16_16") (pintype "passive"))
      (node (ref "U9") (pin "17") (pinfunction "O2_17") (pintype "passive"))
    )
    (net (code "92") (name "/MLL-PWM2") (class "Default")
      (node (ref "CN-B") (pin "18") (pinfunction "18_18") (pintype "passive"))
      (node (ref "U9") (pin "18") (pinfunction "O1_18") (pintype "passive"))
    )
    (net (code "93") (name "/MLL-PWM2_CNT") (class "Default")
      (node (ref "RA7") (pin "2") (pinfunction "2_2") (pintype "passive"))
      (node (ref "U2") (pin "99") (pinfunction "PC9_99") (pintype "bidirectional"))
      (node (ref "U9") (pin "1") (pinfunction "I1_1") (pintype "passive"))
    )
    (net (code "94") (name "/MLL_PWM1_CNT") (class "Default")
      (node (ref "RA7") (pin "3") (pinfunction "3_3") (pintype "passive"))
      (node (ref "U2") (pin "98") (pinfunction "PC8_98") (pintype "bidirectional"))
      (node (ref "U9") (pin "2") (pinfunction "I2_2") (pintype "passive"))
    )
    (net (code "95") (name "/MLR-PG_B") (class "Default")
      (node (ref "U2") (pin "82") (pinfunction "PD13_82") (pintype "bidirectional"))
      (node (ref "U4") (pin "16") (pinfunction "~{Y}3_16") (pintype "tri_state"))
    )
    (net (code "96") (name "/MLR-PG_F") (class "Default")
      (node (ref "U2") (pin "81") (pinfunction "PD12_81") (pintype "bidirectional"))
      (node (ref "U4") (pin "15") (pinfunction "~{Y}4_15") (pintype "tri_state"))
    )
    (net (code "97") (name "/MLR-PWM1") (class "Default")
      (node (ref "CN-B") (pin "15") (pinfunction "15_15") (pintype "passive"))
      (node (ref "U8") (pin "17") (pinfunction "O2_17") (pintype "passive"))
    )
    (net (code "98") (name "/MLR-PWM1_CNT") (class "Default")
      (node (ref "RA6") (pin "3") (pinfunction "3_3") (pintype "passive"))
      (node (ref "U2") (pin "96") (pinfunction "PC6_96") (pintype "bidirectional"))
      (node (ref "U8") (pin "2") (pinfunction "I2_2") (pintype "passive"))
    )
    (net (code "99") (name "/MLR-PWM2") (class "Default")
      (node (ref "CN-B") (pin "17") (pinfunction "17_17") (pintype "passive"))
      (node (ref "U8") (pin "18") (pinfunction "O1_18") (pintype "passive"))
    )
    (net (code "100") (name "/MLR-PWM2_CNT") (class "Default")
      (node (ref "RA6") (pin "2") (pinfunction "2_2") (pintype "passive"))
      (node (ref "U2") (pin "97") (pinfunction "PC7_97") (pintype "bidirectional"))
      (node (ref "U8") (pin "1") (pinfunction "I1_1") (pintype "passive"))
    )
    (net (code "101") (name "/MOTOR-PWR1_CNT") (class "Default")
      (node (ref "RA5") (pin "3") (pinfunction "3_3") (pintype "passive"))
      (node (ref "U2") (pin "70") (pinfunction "PB11_70") (pintype "bidirectional"))
      (node (ref "U7") (pin "2") (pinfunction "I2_2") (pintype "passive"))
    )
    (net (code "102") (name "/MOTOR-PWR2_CNT") (class "Default")
      (node (ref "RA5") (pin "2") (pinfunction "2_2") (pintype "passive"))
      (node (ref "U2") (pin "73") (pinfunction "PB12_73") (pintype "bidirectional"))
      (node (ref "U7") (pin "1") (pinfunction "I1_1") (pintype "passive"))
    )
    (net (code "103") (name "/MR-ALM") (class "Default")
      (node (ref "U2") (pin "117") (pinfunction "PD3_117") (pintype "bidirectional"))
      (node (ref "U4") (pin "14") (pinfunction "~{Y}5_14") (pintype "tri_state"))
    )
    (net (code "104") (name "/MR-BRAKE_CNT") (class "Default")
      (node (ref "RA6") (pin "6") (pinfunction "6_6") (pintype "passive"))
      (node (ref "U2") (pin "115") (pinfunction "PD1_115") (pintype "bidirectional"))
      (node (ref "U8") (pin "5") (pinfunction "I5_5") (pintype "passive"))
    )
    (net (code "105") (name "/MR-ENB_CNT") (class "Default")
      (node (ref "RA6") (pin "5") (pinfunction "5_5") (pintype "passive"))
      (node (ref "U2") (pin "116") (pinfunction "PD2_116") (pintype "bidirectional"))
      (node (ref "U8") (pin "4") (pinfunction "I4_4") (pintype "passive"))
    )
    (net (code "106") (name "/MR-F{slash}*R_CNT") (class "Default")
      (node (ref "RA6") (pin "7") (pinfunction "7_7") (pintype "passive"))
      (node (ref "U2") (pin "114") (pinfunction "PD0_114") (pintype "bidirectional"))
      (node (ref "U8") (pin "6") (pinfunction "I6_6") (pintype "passive"))
    )
    (net (code "107") (name "/MR-PG") (class "Default")
      (node (ref "U2") (pin "77") (pinfunction "PD8_77") (pintype "bidirectional"))
      (node (ref "U4") (pin "13") (pinfunction "~{Y}6_13") (pintype "tri_state"))
    )
    (net (code "108") (name "/MR-PWM") (class "Default")
      (node (ref "CN-B") (pin "13") (pinfunction "13_13") (pintype "passive"))
      (node (ref "U8") (pin "16") (pinfunction "O3_16") (pintype "passive"))
    )
    (net (code "109") (name "/MR-PWM_CNT") (class "Default")
      (node (ref "RA6") (pin "4") (pinfunction "4_4") (pintype "passive"))
      (node (ref "U2") (pin "34") (pinfunction "PA0-WKUP_34") (pintype "bidirectional"))
      (node (ref "U8") (pin "3") (pinfunction "I3_3") (pintype "passive"))
    )
    (net (code "110") (name "/PCM-CK") (class "Default")
      (node (ref "CN-B") (pin "35") (pinfunction "35_35") (pintype "passive"))
    )
    (net (code "111") (name "/PCM-DI") (class "Default")
      (node (ref "CN-B") (pin "34") (pinfunction "34_34") (pintype "passive"))
    )
    (net (code "112") (name "/PCM-DO") (class "Default")
      (node (ref "CN-B") (pin "33") (pinfunction "33_33") (pintype "passive"))
    )
    (net (code "113") (name "/PCM-SYNC") (class "Default")
      (node (ref "CN-B") (pin "36") (pinfunction "36_36") (pintype "passive"))
    )
    (net (code "114") (name "/RESET") (class "Default")
      (node (ref "J-SW") (pin "2") (pinfunction "2_2") (pintype "passive"))
      (node (ref "R5") (pin "1") (pinfunction "1_1") (pintype "passive"))
      (node (ref "U1") (pin "1") (pinfunction "O_1") (pintype "passive"))
      (node (ref "U2") (pin "25") (pinfunction "NRST_25") (pintype "bidirectional"))
    )
    (net (code "115") (name "/Sns-BRAKE_Curr") (class "Default")
      (node (ref "CN-C") (pin "36") (pinfunction "36_36") (pintype "passive"))
      (node (ref "U2") (pin "29") (pinfunction "PC3_29") (pintype "bidirectional"))
    )
    (net (code "116") (name "/Sns-COVER") (class "Default")
      (node (ref "U2") (pin "5") (pinfunction "PE6_5") (pintype "bidirectional"))
      (node (ref "U3") (pin "16") (pinfunction "~{Y}3_16") (pintype "tri_state"))
    )
    (net (code "117") (name "/Sns-HOME_C") (class "Default")
      (node (ref "U2") (pin "66") (pinfunction "PE13_66") (pintype "bidirectional"))
      (node (ref "U3") (pin "13") (pinfunction "~{Y}6_13") (pintype "tri_state"))
    )
    (net (code "118") (name "/Sns-HOME_L") (class "Default")
      (node (ref "U2") (pin "65") (pinfunction "PE12_65") (pintype "bidirectional"))
      (node (ref "U3") (pin "11") (pinfunction "~{Y}8_11") (pintype "tri_state"))
    )
    (net (code "119") (name "/Sns-HOME_R") (class "Default")
      (node (ref "U2") (pin "67") (pinfunction "PE14_67") (pintype "bidirectional"))
      (node (ref "U3") (pin "12") (pinfunction "~{Y}7_12") (pintype "tri_state"))
    )
    (net (code "120") (name "/Sns-Lug-Curr") (class "Default")
      (node (ref "CN-C") (pin "37") (pinfunction "37_37") (pintype "passive"))
      (node (ref "U2") (pin "26") (pinfunction "PC0_26") (pintype "bidirectional"))
    )
    (net (code "121") (name "/Sns-MIC_CLOSE") (class "Default")
      (node (ref "U2") (pin "56") (pinfunction "PG0_56") (pintype "bidirectional"))
      (node (ref "U3") (pin "15") (pinfunction "~{Y}4_15") (pintype "tri_state"))
    )
    (net (code "122") (name "/Sns-MLL_Curr") (class "Default")
      (node (ref "CN-C") (pin "38") (pinfunction "38_38") (pintype "passive"))
      (node (ref "U2") (pin "27") (pinfunction "PC1_27") (pintype "bidirectional"))
    )
    (net (code "123") (name "/Sns-MLR_Curr") (class "Default")
      (node (ref "CN-C") (pin "35") (pinfunction "35_35") (pintype "passive"))
      (node (ref "U2") (pin "28") (pinfunction "PC2_28") (pintype "bidirectional"))
    )
    (net (code "124") (name "/Sns-RAIN") (class "Default")
      (node (ref "U2") (pin "89") (pinfunction "PG4_89") (pintype "bidirectional"))
      (node (ref "U3") (pin "17") (pinfunction "~{Y}2_17") (pintype "tri_state"))
    )
    (net (code "125") (name "/Sns-US_EMG") (class "Default")
      (node (ref "U2") (pin "90") (pinfunction "PG5_90") (pintype "bidirectional"))
      (node (ref "U3") (pin "18") (pinfunction "~{Y}1_18") (pintype "tri_state"))
    )
    (net (code "126") (name "/UART-CB_Rx") (class "Default")
      (node (ref "CN-A") (pin "22") (pinfunction "22_22") (pintype "passive"))
      (node (ref "U2") (pin "101") (pinfunction "PA9_101") (pintype "bidirectional"))
    )
    (net (code "127") (name "/UART-CB_Tx") (class "Default")
      (node (ref "CN-A") (pin "21") (pinfunction "21_21") (pintype "passive"))
      (node (ref "U2") (pin "102") (pinfunction "PA10_102") (pintype "bidirectional"))
    )
    (net (code "128") (name "/UART-DB_Rx") (class "Default")
      (node (ref "J-DB") (pin "3") (pinfunction "3_3") (pintype "passive"))
      (node (ref "U2") (pin "36") (pinfunction "PA2_36") (pintype "bidirectional"))
    )
    (net (code "129") (name "/UART-DB_Tx") (class "Default")
      (node (ref "J-DB") (pin "2") (pinfunction "2_2") (pintype "passive"))
      (node (ref "U2") (pin "37") (pinfunction "PA3_37") (pintype "bidirectional"))
    )
    (net (code "130") (name "/USB-DM") (class "Default")
      (node (ref "R1") (pin "1") (pinfunction "1_1") (pintype "passive"))
      (node (ref "U2") (pin "103") (pinfunction "PA11_103") (pintype "bidirectional"))
    )
    (net (code "131") (name "/USB-DP") (class "Default")
      (node (ref "R2") (pin "1") (pinfunction "1_1") (pintype "passive"))
      (node (ref "U2") (pin "104") (pinfunction "PA12_104") (pintype "bidirectional"))
    )
    (net (code "132") (name "/USB_5V") (class "Default")
      (node (ref "CN-A") (pin "10") (pinfunction "10_10") (pintype "passive"))
      (node (ref "CN-A") (pin "9") (pinfunction "9_9") (pintype "passive"))
    )
    (net (code "133") (name "/USB_DM1") (class "Default")
      (node (ref "CN-A") (pin "11") (pinfunction "11_11") (pintype "passive"))
    )
    (net (code "134") (name "/USB_DM2") (class "Default")
      (node (ref "CN-A") (pin "12") (pinfunction "12_12") (pintype "passive"))
    )
    (net (code "135") (name "/USB_DP1") (class "Default")
      (node (ref "CN-A") (pin "13") (pinfunction "13_13") (pintype "passive"))
    )
    (net (code "136") (name "/USB_DP2") (class "Default")
      (node (ref "CN-A") (pin "14") (pinfunction "14_14") (pintype "passive"))
    )
    (net (code "137") (name "/USB_POWER") (class "Default")
      (node (ref "CN-A") (pin "30") (pinfunction "30_30") (pintype "passive"))
      (node (ref "U2") (pin "111") (pinfunction "PC10_111") (pintype "bidirectional"))
    )
    (net (code "138") (name "/US_EMG") (class "Default")
      (node (ref "CN-A") (pin "26") (pinfunction "26_26") (pintype "passive"))
      (node (ref "RA1") (pin "2") (pinfunction "2_2") (pintype "passive"))
      (node (ref "U3") (pin "2") (pinfunction "A1_2") (pintype "input"))
    )
    (net (code "139") (name "/US_POWER") (class "Default")
      (node (ref "CN-A") (pin "32") (pinfunction "32_32") (pintype "passive"))
      (node (ref "U2") (pin "112") (pinfunction "PC11_112") (pintype "bidirectional"))
    )
    (net (code "140") (name "DC3.3V") (class "Default")
      (node (ref "C10") (pin "2") (pinfunction "2_2") (pintype "passive"))
      (node (ref "C11") (pin "2") (pinfunction "2_2") (pintype "passive"))
      (node (ref "C12") (pin "2") (pinfunction "2_2") (pintype "passive"))
      (node (ref "C3") (pin "2") (pinfunction "2_2") (pintype "passive"))
      (node (ref "C4") (pin "2") (pinfunction "2_2") (pintype "passive"))
      (node (ref "C5") (pin "2") (pinfunction "2_2") (pintype "passive"))
      (node (ref "C6") (pin "2") (pinfunction "2_2") (pintype "passive"))
      (node (ref "CN-A") (pin "7") (pinfunction "7_7") (pintype "passive"))
      (node (ref "CN-A") (pin "8") (pinfunction "8_8") (pintype "passive"))
      (node (ref "D1") (pin "1") (pinfunction "A_1") (pintype "passive"))
      (node (ref "J-DB") (pin "1") (pinfunction "1_1") (pintype "passive"))
      (node (ref "J-EXT") (pin "1") (pinfunction "1_1") (pintype "passive"))
      (node (ref "J-SW") (pin "1") (pinfunction "1_1") (pintype "passive"))
      (node (ref "R5") (pin "2") (pinfunction "2_2") (pintype "passive"))
      (node (ref "RA1") (pin "1") (pinfunction "1_1") (pintype "passive"))
      (node (ref "RA2") (pin "1") (pinfunction "1_1") (pintype "passive"))
      (node (ref "RA3") (pin "1") (pinfunction "1_1") (pintype "passive"))
      (node (ref "RA4") (pin "1") (pinfunction "1_1") (pintype "passive"))
      (node (ref "RA5") (pin "1") (pinfunction "1_1") (pintype "passive"))
      (node (ref "RA6") (pin "1") (pinfunction "1_1") (pintype "passive"))
      (node (ref "RA7") (pin "1") (pinfunction "1_1") (pintype "passive"))
      (node (ref "RA8") (pin "1") (pinfunction "1_1") (pintype "passive"))
      (node (ref "RA9") (pin "1") (pinfunction "1_1") (pintype "passive"))
      (node (ref "U1") (pin "2") (pinfunction "V_2") (pintype "passive"))
      (node (ref "U2") (pin "108") (pinfunction "VDD_2_108") (pintype "power_in"))
      (node (ref "U2") (pin "121") (pinfunction "VDD_10_121") (pintype "power_in"))
      (node (ref "U2") (pin "131") (pinfunction "VDD_11_131") (pintype "power_in"))
      (node (ref "U2") (pin "144") (pinfunction "VDD_3_144") (pintype "power_in"))
      (node (ref "U2") (pin "17") (pinfunction "VDD_5_17") (pintype "power_in"))
      (node (ref "U2") (pin "33") (pinfunction "VDDA_33") (pintype "power_in"))
      (node (ref "U2") (pin "39") (pinfunction "VDD_4_39") (pintype "power_in"))
      (node (ref "U2") (pin "52") (pinfunction "VDD_6_52") (pintype "power_in"))
      (node (ref "U2") (pin "62") (pinfunction "VDD_7_62") (pintype "power_in"))
      (node (ref "U2") (pin "72") (pinfunction "VDD_1_72") (pintype "power_in"))
      (node (ref "U2") (pin "84") (pinfunction "VDD_8_84") (pintype "power_in"))
      (node (ref "U2") (pin "95") (pinfunction "VDD_9_95") (pintype "power_in"))
      (node (ref "U3") (pin "20") (pinfunction "VCC_20") (pintype "power_in"))
      (node (ref "U4") (pin "20") (pinfunction "VCC_20") (pintype "power_in"))
      (node (ref "U5") (pin "20") (pinfunction "VCC_20") (pintype "power_in"))
    )
    (net (code "141") (name "GND") (class "Default")
      (node (ref "C1") (pin "2") (pinfunction "2_2") (pintype "passive"))
      (node (ref "C10") (pin "1") (pinfunction "1_1") (pintype "passive"))
      (node (ref "C11") (pin "1") (pinfunction "1_1") (pintype "passive"))
      (node (ref "C12") (pin "1") (pinfunction "1_1") (pintype "passive"))
      (node (ref "C2") (pin "2") (pinfunction "2_2") (pintype "passive"))
      (node (ref "C3") (pin "1") (pinfunction "1_1") (pintype "passive"))
      (node (ref "C4") (pin "1") (pinfunction "1_1") (pintype "passive"))
      (node (ref "C5") (pin "1") (pinfunction "1_1") (pintype "passive"))
      (node (ref "C6") (pin "1") (pinfunction "1_1") (pintype "passive"))
      (node (ref "C8") (pin "1") (pinfunction "1_1") (pintype "passive"))
      (node (ref "C9") (pin "1") (pinfunction "1_1") (pintype "passive"))
      (node (ref "CN-A") (pin "35") (pinfunction "35_35") (pintype "passive"))
      (node (ref "CN-A") (pin "36") (pinfunction "36_36") (pintype "passive"))
      (node (ref "CN-A") (pin "37") (pinfunction "37_37") (pintype "passive"))
      (node (ref "CN-A") (pin "38") (pinfunction "38_38") (pintype "passive"))
      (node (ref "CN-A") (pin "39") (pinfunction "39_39") (pintype "passive"))
      (node (ref "CN-A") (pin "40") (pinfunction "40_40") (pintype "passive"))
      (node (ref "CN-B") (pin "39") (pinfunction "39_39") (pintype "passive"))
      (node (ref "CN-B") (pin "40") (pinfunction "40_40") (pintype "passive"))
      (node (ref "CN-C") (pin "39") (pinfunction "39_39") (pintype "passive"))
      (node (ref "CN-C") (pin "40") (pinfunction "40_40") (pintype "passive"))
      (node (ref "DCR1") (pin "2") (pinfunction "2_2") (pintype "power_in"))
      (node (ref "J-DB") (pin "4") (pinfunction "4_4") (pintype "passive"))
      (node (ref "J-EXT") (pin "10") (pinfunction "10_10") (pintype "passive"))
      (node (ref "J-SW") (pin "10") (pinfunction "10_10") (pintype "passive"))
      (node (ref "J-USB") (pin "5") (pinfunction "GND_5") (pintype "passive"))
      (node (ref "R3") (pin "1") (pinfunction "1_1") (pintype "passive"))
      (node (ref "R6") (pin "2") (pinfunction "2_2") (pintype "passive"))
      (node (ref "R7") (pin "2") (pinfunction "2_2") (pintype "passive"))
      (node (ref "U1") (pin "3") (pinfunction "G_3") (pintype "passive"))
      (node (ref "U2") (pin "107") (pinfunction "VSS_2_107") (pintype "power_in"))
      (node (ref "U2") (pin "120") (pinfunction "VSS_10_120") (pintype "power_in"))
      (node (ref "U2") (pin "130") (pinfunction "VSS_11_130") (pintype "power_in"))
      (node (ref "U2") (pin "143") (pinfunction "VSS_3_143") (pintype "power_in"))
      (node (ref "U2") (pin "16") (pinfunction "VSS_5_16") (pintype "power_in"))
      (node (ref "U2") (pin "30") (pinfunction "VSSA_30") (pintype "power_in"))
      (node (ref "U2") (pin "38") (pinfunction "VSS_4_38") (pintype "power_in"))
      (node (ref "U2") (pin "51") (pinfunction "VSS_6_51") (pintype "power_in"))
      (node (ref "U2") (pin "61") (pinfunction "VSS_7_61") (pintype "power_in"))
      (node (ref "U2") (pin "71") (pinfunction "VSS_1_71") (pintype "power_in"))
      (node (ref "U2") (pin "83") (pinfunction "VSS_8_83") (pintype "power_in"))
      (node (ref "U2") (pin "94") (pinfunction "VSS_9_94") (pintype "power_in"))
      (node (ref "U3") (pin "1") (pinfunction "~{OE}1_1") (pintype "input"))
      (node (ref "U3") (pin "10") (pinfunction "GND_10") (pintype "power_in"))
      (node (ref "U3") (pin "19") (pinfunction "~{OE}2_19") (pintype "input"))
      (node (ref "U4") (pin "1") (pinfunction "~{OE}1_1") (pintype "input"))
      (node (ref "U4") (pin "10") (pinfunction "GND_10") (pintype "power_in"))
      (node (ref "U4") (pin "19") (pinfunction "~{OE}2_19") (pintype "input"))
      (node (ref "U5") (pin "1") (pinfunction "~{OE}1_1") (pintype "input"))
      (node (ref "U5") (pin "10") (pinfunction "GND_10") (pintype "power_in"))
      (node (ref "U5") (pin "19") (pinfunction "~{OE}2_19") (pintype "input"))
      (node (ref "U7") (pin "9") (pinfunction "GND_9") (pintype "passive"))
      (node (ref "U8") (pin "9") (pinfunction "GND_9") (pintype "passive"))
      (node (ref "U9") (pin "9") (pinfunction "GND_9") (pintype "passive"))
    )
    (net (code "142") (name "Net-(D1-K)") (class "Default")
      (node (ref "D1") (pin "2") (pinfunction "K_2") (pintype "passive"))
      (node (ref "JP1") (pin "1") (pinfunction "C1_1") (pintype "passive"))
    )
    (net (code "143") (name "Net-(J-USB-D+)") (class "Default")
      (node (ref "J-USB") (pin "3") (pinfunction "D+_3") (pintype "passive"))
      (node (ref "R2") (pin "2") (pinfunction "2_2") (pintype "passive"))
    )
    (net (code "144") (name "Net-(J-USB-D-)") (class "Default")
      (node (ref "J-USB") (pin "2") (pinfunction "D-_2") (pintype "passive"))
      (node (ref "R1") (pin "2") (pinfunction "2_2") (pintype "passive"))
    )
    (net (code "145") (name "Net-(J-USB-ID)") (class "Default")
      (node (ref "J-USB") (pin "4") (pinfunction "ID_4") (pintype "passive"))
      (node (ref "R3") (pin "2") (pinfunction "2_2") (pintype "passive"))
    )
    (net (code "146") (name "Net-(JP1-C2)") (class "Default")
      (node (ref "C8") (pin "2") (pinfunction "2_2") (pintype "passive"))
      (node (ref "DCR1") (pin "3") (pinfunction "3_3") (pintype "power_in"))
      (node (ref "JP1") (pin "2") (pinfunction "C2_2") (pintype "passive"))
    )
    (net (code "147") (name "Net-(U2B-OSC_IN)") (class "Default")
      (node (ref "C1") (pin "1") (pinfunction "1_1") (pintype "passive"))
      (node (ref "U2") (pin "23") (pinfunction "OSC_IN_23") (pintype "input"))
      (node (ref "X1") (pin "2") (pinfunction "OSC2_2") (pintype "passive"))
    )
    (net (code "148") (name "Net-(U2B-OSC_OUT)") (class "Default")
      (node (ref "C2") (pin "1") (pinfunction "1_1") (pintype "passive"))
      (node (ref "U2") (pin "24") (pinfunction "OSC_OUT_24") (pintype "passive"))
      (node (ref "X1") (pin "1") (pinfunction "OSC1_1") (pintype "passive"))
    )
    (net (code "149") (name "Net-(U3-A5)") (class "Default")
      (node (ref "RA1") (pin "6") (pinfunction "6_6") (pintype "passive"))
      (node (ref "U3") (pin "6") (pinfunction "A5_6") (pintype "input"))
    )
    (net (code "150") (name "Net-(U4-A1)") (class "Default")
      (node (ref "RA2") (pin "2") (pinfunction "2_2") (pintype "passive"))
      (node (ref "U4") (pin "2") (pinfunction "A1_2") (pintype "input"))
    )
    (net (code "151") (name "Net-(U4-A2)") (class "Default")
      (node (ref "RA2") (pin "3") (pinfunction "3_3") (pintype "passive"))
      (node (ref "U4") (pin "3") (pinfunction "A2_3") (pintype "input"))
    )
    (net (code "152") (name "Net-(U4-A7)") (class "Default")
      (node (ref "RA2") (pin "8") (pinfunction "8_8") (pintype "passive"))
      (node (ref "U4") (pin "8") (pinfunction "A7_8") (pintype "input"))
    )
    (net (code "153") (name "Net-(U4-A8)") (class "Default")
      (node (ref "RA2") (pin "9") (pinfunction "9_9") (pintype "passive"))
      (node (ref "U4") (pin "9") (pinfunction "A8_9") (pintype "input"))
    )
    (net (code "154") (name "Net-(U5-A1)") (class "Default")
      (node (ref "RA3") (pin "2") (pinfunction "2_2") (pintype "passive"))
      (node (ref "U5") (pin "2") (pinfunction "A1_2") (pintype "input"))
    )
    (net (code "155") (name "Net-(U5-A2)") (class "Default")
      (node (ref "RA3") (pin "3") (pinfunction "3_3") (pintype "passive"))
      (node (ref "U5") (pin "3") (pinfunction "A2_3") (pintype "input"))
    )
    (net (code "156") (name "Net-(U5-A7)") (class "Default")
      (node (ref "RA3") (pin "8") (pinfunction "8_8") (pintype "passive"))
      (node (ref "U5") (pin "8") (pinfunction "A7_8") (pintype "input"))
    )
    (net (code "157") (name "Net-(U5-A8)") (class "Default")
      (node (ref "RA3") (pin "9") (pinfunction "9_9") (pintype "passive"))
      (node (ref "U5") (pin "9") (pinfunction "A8_9") (pintype "input"))
    )
    (net (code "158") (name "Net-(U8-I8)") (class "Default")
      (node (ref "RA6") (pin "9") (pinfunction "9_9") (pintype "passive"))
      (node (ref "U8") (pin "8") (pinfunction "I8_8") (pintype "passive"))
    )
    (net (code "159") (name "Net-(U9-I8)") (class "Default")
      (node (ref "RA7") (pin "9") (pinfunction "9_9") (pintype "passive"))
      (node (ref "U9") (pin "8") (pinfunction "I8_8") (pintype "passive"))
    )
    (net (code "160") (name "U5V") (class "Default")
      (node (ref "C9") (pin "2") (pinfunction "2_2") (pintype "passive"))
      (node (ref "DCR1") (pin "1") (pinfunction "1_1") (pintype "power_in"))
      (node (ref "J-USB") (pin "1") (pinfunction "Vcc_1") (pintype "passive"))
    )
    (net (code "161") (name "unconnected-(CN-A-Pad15)") (class "Default")
      (node (ref "CN-A") (pin "15") (pinfunction "15_15") (pintype "passive"))
    )
    (net (code "162") (name "unconnected-(CN-A-Pad16)") (class "Default")
      (node (ref "CN-A") (pin "16") (pinfunction "16_16") (pintype "passive"))
    )
    (net (code "163") (name "unconnected-(CN-A-Pad23)") (class "Default")
      (node (ref "CN-A") (pin "23") (pinfunction "23_23") (pintype "passive"))
    )
    (net (code "164") (name "unconnected-(CN-A-Pad24)") (class "Default")
      (node (ref "CN-A") (pin "24") (pinfunction "24_24") (pintype "passive"))
    )
    (net (code "165") (name "unconnected-(CN-A-Pad27)") (class "Default")
      (node (ref "CN-A") (pin "27") (pinfunction "27_27") (pintype "passive"))
    )
    (net (code "166") (name "unconnected-(CN-A-Pad28)") (class "Default")
      (node (ref "CN-A") (pin "28") (pinfunction "28_28") (pintype "passive"))
    )
    (net (code "167") (name "unconnected-(CN-A-Pad34)") (class "Default")
      (node (ref "CN-A") (pin "34") (pinfunction "34_34") (pintype "passive"))
    )
    (net (code "168") (name "unconnected-(CN-B-Pad2)") (class "Default")
      (node (ref "CN-B") (pin "2") (pinfunction "2_2") (pintype "passive"))
    )
    (net (code "169") (name "unconnected-(CN-B-Pad4)") (class "Default")
      (node (ref "CN-B") (pin "4") (pinfunction "4_4") (pintype "passive"))
    )
    (net (code "170") (name "unconnected-(CN-B-Pad6)") (class "Default")
      (node (ref "CN-B") (pin "6") (pinfunction "6_6") (pintype "passive"))
    )
    (net (code "171") (name "unconnected-(CN-B-Pad20)") (class "Default")
      (node (ref "CN-B") (pin "20") (pinfunction "20_20") (pintype "passive"))
    )
    (net (code "172") (name "unconnected-(CN-B-Pad22)") (class "Default")
      (node (ref "CN-B") (pin "22") (pinfunction "22_22") (pintype "passive"))
    )
    (net (code "173") (name "unconnected-(CN-B-Pad24)") (class "Default")
      (node (ref "CN-B") (pin "24") (pinfunction "24_24") (pintype "passive"))
    )
    (net (code "174") (name "unconnected-(CN-B-Pad26)") (class "Default")
      (node (ref "CN-B") (pin "26") (pinfunction "26_26") (pintype "passive"))
    )
    (net (code "175") (name "unconnected-(CN-B-Pad27)") (class "Default")
      (node (ref "CN-B") (pin "27") (pinfunction "27_27") (pintype "passive"))
    )
    (net (code "176") (name "unconnected-(CN-B-Pad28)") (class "Default")
      (node (ref "CN-B") (pin "28") (pinfunction "28_28") (pintype "passive"))
    )
    (net (code "177") (name "unconnected-(CN-B-Pad29)") (class "Default")
      (node (ref "CN-B") (pin "29") (pinfunction "29_29") (pintype "passive"))
    )
    (net (code "178") (name "unconnected-(CN-B-Pad30)") (class "Default")
      (node (ref "CN-B") (pin "30") (pinfunction "30_30") (pintype "passive"))
    )
    (net (code "179") (name "unconnected-(CN-B-Pad31)") (class "Default")
      (node (ref "CN-B") (pin "31") (pinfunction "31_31") (pintype "passive"))
    )
    (net (code "180") (name "unconnected-(CN-B-Pad32)") (class "Default")
      (node (ref "CN-B") (pin "32") (pinfunction "32_32") (pintype "passive"))
    )
    (net (code "181") (name "unconnected-(CN-B-Pad37)") (class "Default")
      (node (ref "CN-B") (pin "37") (pinfunction "37_37") (pintype "passive"))
    )
    (net (code "182") (name "unconnected-(CN-B-Pad38)") (class "Default")
      (node (ref "CN-B") (pin "38") (pinfunction "38_38") (pintype "passive"))
    )
    (net (code "183") (name "unconnected-(RA8-Pad8)") (class "Default")
      (node (ref "RA8") (pin "8") (pinfunction "8_8") (pintype "passive"))
    )
    (net (code "184") (name "unconnected-(RA8-Pad9)") (class "Default")
      (node (ref "RA8") (pin "9") (pinfunction "9_9") (pintype "passive"))
    )
    (net (code "185") (name "unconnected-(U1---Pad4)") (class "Default")
      (node (ref "U1") (pin "4") (pinfunction "-_4") (pintype "passive"))
    )
    (net (code "186") (name "unconnected-(U1---Pad5)") (class "Default")
      (node (ref "U1") (pin "5") (pinfunction "-_5") (pintype "power_in"))
    )
    (net (code "187") (name "unconnected-(U2A-PA5-Pad41)") (class "Default")
      (node (ref "U2") (pin "41") (pinfunction "PA5_41") (pintype "bidirectional"))
    )
    (net (code "188") (name "unconnected-(U2A-PB5-Pad135)") (class "Default")
      (node (ref "U2") (pin "135") (pinfunction "PB5_135") (pintype "bidirectional"))
    )
    (net (code "189") (name "unconnected-(U2A-PB15-Pad76)") (class "Default")
      (node (ref "U2") (pin "76") (pinfunction "PB15_76") (pintype "bidirectional"))
    )
    (net (code "190") (name "unconnected-(U2A-PC5-Pad45)") (class "Default")
      (node (ref "U2") (pin "45") (pinfunction "PC5_45") (pintype "bidirectional"))
    )
    (net (code "191") (name "unconnected-(U2A-PC12-Pad113)") (class "Default")
      (node (ref "U2") (pin "113") (pinfunction "PC12_113") (pintype "bidirectional"))
    )
    (net (code "192") (name "unconnected-(U2A-PC13-TAMPER-RTC-Pad7)") (class "Default")
      (node (ref "U2") (pin "7") (pinfunction "PC13-TAMPER-RTC_7") (pintype "bidirectional"))
    )
    (net (code "193") (name "unconnected-(U2A-PC14-OSC32_IN-Pad8)") (class "Default")
      (node (ref "U2") (pin "8") (pinfunction "PC14-OSC32_IN_8") (pintype "bidirectional"))
    )
    (net (code "194") (name "unconnected-(U2A-PC15-OSC32_OUT-Pad9)") (class "Default")
      (node (ref "U2") (pin "9") (pinfunction "PC15-OSC32_OUT_9") (pintype "bidirectional"))
    )
    (net (code "195") (name "unconnected-(U2A-PD10-Pad79)") (class "Default")
      (node (ref "U2") (pin "79") (pinfunction "PD10_79") (pintype "bidirectional"))
    )
    (net (code "196") (name "unconnected-(U2A-PD11-Pad80)") (class "Default")
      (node (ref "U2") (pin "80") (pinfunction "PD11_80") (pintype "bidirectional"))
    )
    (net (code "197") (name "unconnected-(U2B-NC-Pad106)") (class "Default")
      (node (ref "U2") (pin "106") (pinfunction "NC_106") (pintype "passive"))
    )
    (net (code "198") (name "unconnected-(U2B-PE0-Pad141)") (class "Default")
      (node (ref "U2") (pin "141") (pinfunction "PE0_141") (pintype "bidirectional"))
    )
    (net (code "199") (name "unconnected-(U2B-PE1-Pad142)") (class "Default")
      (node (ref "U2") (pin "142") (pinfunction "PE1_142") (pintype "bidirectional"))
    )
    (net (code "200") (name "unconnected-(U2B-PE15-Pad68)") (class "Default")
      (node (ref "U2") (pin "68") (pinfunction "PE15_68") (pintype "bidirectional"))
    )
    (net (code "201") (name "unconnected-(U2B-PF8-Pad20)") (class "Default")
      (node (ref "U2") (pin "20") (pinfunction "PF8_20") (pintype "bidirectional"))
    )
    (net (code "202") (name "unconnected-(U2B-PF9-Pad21)") (class "Default")
      (node (ref "U2") (pin "21") (pinfunction "PF9_21") (pintype "bidirectional"))
    )
    (net (code "203") (name "unconnected-(U2B-PF10-Pad22)") (class "Default")
      (node (ref "U2") (pin "22") (pinfunction "PF10_22") (pintype "bidirectional"))
    )
    (net (code "204") (name "unconnected-(U2B-PF11-Pad49)") (class "Default")
      (node (ref "U2") (pin "49") (pinfunction "PF11_49") (pintype "bidirectional"))
    )
    (net (code "205") (name "unconnected-(U2B-PF12-Pad50)") (class "Default")
      (node (ref "U2") (pin "50") (pinfunction "PF12_50") (pintype "bidirectional"))
    )
    (net (code "206") (name "unconnected-(U2B-PF13-Pad53)") (class "Default")
      (node (ref "U2") (pin "53") (pinfunction "PF13_53") (pintype "bidirectional"))
    )
    (net (code "207") (name "unconnected-(U2B-PF14-Pad54)") (class "Default")
      (node (ref "U2") (pin "54") (pinfunction "PF14_54") (pintype "bidirectional"))
    )
    (net (code "208") (name "unconnected-(U2B-PF15-Pad55)") (class "Default")
      (node (ref "U2") (pin "55") (pinfunction "PF15_55") (pintype "bidirectional"))
    )
    (net (code "209") (name "unconnected-(U2B-PG9-Pad124)") (class "Default")
      (node (ref "U2") (pin "124") (pinfunction "PG9_124") (pintype "bidirectional"))
    )
    (net (code "210") (name "unconnected-(U2B-PG10-Pad125)") (class "Default")
      (node (ref "U2") (pin "125") (pinfunction "PG10_125") (pintype "bidirectional"))
    )
    (net (code "211") (name "unconnected-(U2B-PG11-Pad126)") (class "Default")
      (node (ref "U2") (pin "126") (pinfunction "PG11_126") (pintype "bidirectional"))
    )
    (net (code "212") (name "unconnected-(U2B-PG12-Pad127)") (class "Default")
      (node (ref "U2") (pin "127") (pinfunction "PG12_127") (pintype "bidirectional"))
    )
    (net (code "213") (name "unconnected-(U2B-PG13-Pad128)") (class "Default")
      (node (ref "U2") (pin "128") (pinfunction "PG13_128") (pintype "bidirectional"))
    )
    (net (code "214") (name "unconnected-(U2B-PG14-Pad129)") (class "Default")
      (node (ref "U2") (pin "129") (pinfunction "PG14_129") (pintype "bidirectional"))
    )
    (net (code "215") (name "unconnected-(U2B-PG15-Pad132)") (class "Default")
      (node (ref "U2") (pin "132") (pinfunction "PG15_132") (pintype "bidirectional"))
    )
    (net (code "216") (name "unconnected-(U2C-VBAT-Pad6)") (class "Default")
      (node (ref "U2") (pin "6") (pinfunction "VBAT_6") (pintype "power_in"))
    )
    (net (code "217") (name "unconnected-(U2C-VREF+-Pad32)") (class "Default")
      (node (ref "U2") (pin "32") (pinfunction "VREF+_32") (pintype "power_in"))
    )
    (net (code "218") (name "unconnected-(U2C-VREF--Pad31)") (class "Default")
      (node (ref "U2") (pin "31") (pinfunction "VREF-_31") (pintype "power_in"))
    )
    (net (code "219") (name "unconnected-(U3-~{Y}5-Pad14)") (class "Default")
      (node (ref "U3") (pin "14") (pinfunction "~{Y}5_14") (pintype "tri_state"))
    )
    (net (code "220") (name "unconnected-(U4-~{Y}1-Pad18)") (class "Default")
      (node (ref "U4") (pin "18") (pinfunction "~{Y}1_18") (pintype "tri_state"))
    )
    (net (code "221") (name "unconnected-(U4-~{Y}2-Pad17)") (class "Default")
      (node (ref "U4") (pin "17") (pinfunction "~{Y}2_17") (pintype "tri_state"))
    )
    (net (code "222") (name "unconnected-(U4-~{Y}7-Pad12)") (class "Default")
      (node (ref "U4") (pin "12") (pinfunction "~{Y}7_12") (pintype "tri_state"))
    )
    (net (code "223") (name "unconnected-(U4-~{Y}8-Pad11)") (class "Default")
      (node (ref "U4") (pin "11") (pinfunction "~{Y}8_11") (pintype "tri_state"))
    )
    (net (code "224") (name "unconnected-(U5-~{Y}1-Pad18)") (class "Default")
      (node (ref "U5") (pin "18") (pinfunction "~{Y}1_18") (pintype "tri_state"))
    )
    (net (code "225") (name "unconnected-(U5-~{Y}2-Pad17)") (class "Default")
      (node (ref "U5") (pin "17") (pinfunction "~{Y}2_17") (pintype "tri_state"))
    )
    (net (code "226") (name "unconnected-(U5-~{Y}7-Pad12)") (class "Default")
      (node (ref "U5") (pin "12") (pinfunction "~{Y}7_12") (pintype "tri_state"))
    )
    (net (code "227") (name "unconnected-(U5-~{Y}8-Pad11)") (class "Default")
      (node (ref "U5") (pin "11") (pinfunction "~{Y}8_11") (pintype "tri_state"))
    )
    (net (code "228") (name "unconnected-(U7-COM-Pad10)") (class "Default")
      (node (ref "U7") (pin "10") (pinfunction "COM_10") (pintype "passive"))
    )
    (net (code "229") (name "unconnected-(U8-COM-Pad10)") (class "Default")
      (node (ref "U8") (pin "10") (pinfunction "COM_10") (pintype "passive"))
    )
    (net (code "230") (name "unconnected-(U8-O8-Pad11)") (class "Default")
      (node (ref "U8") (pin "11") (pinfunction "O8_11") (pintype "passive"))
    )
    (net (code "231") (name "unconnected-(U9-COM-Pad10)") (class "Default")
      (node (ref "U9") (pin "10") (pinfunction "COM_10") (pintype "passive"))
    )
    (net (code "232") (name "unconnected-(U9-O8-Pad11)") (class "Default")
      (node (ref "U9") (pin "11") (pinfunction "O8_11") (pintype "passive"))
    )
  )
)
